# Project_Amp_RevA.net
KiCad netlist of a schematic drawn in EAGLE
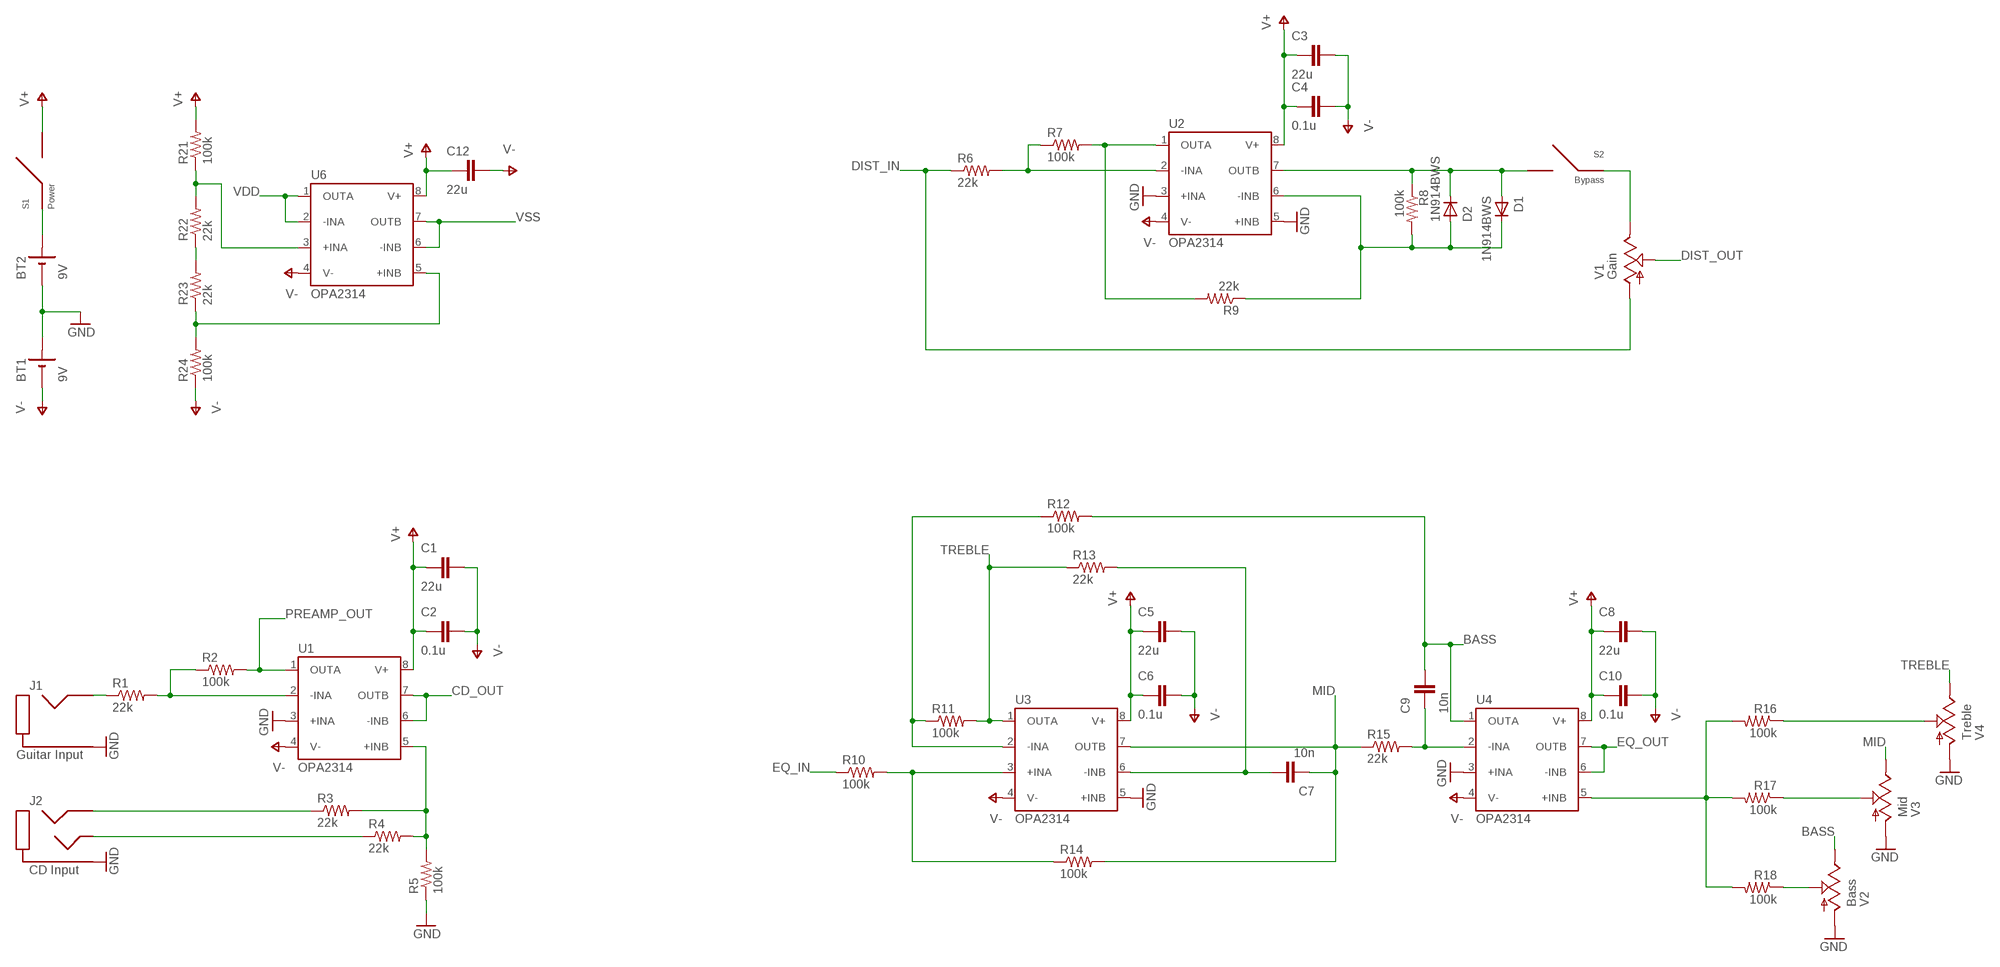
[diagram p0: schematic, sheet 1, part 1 of 2]
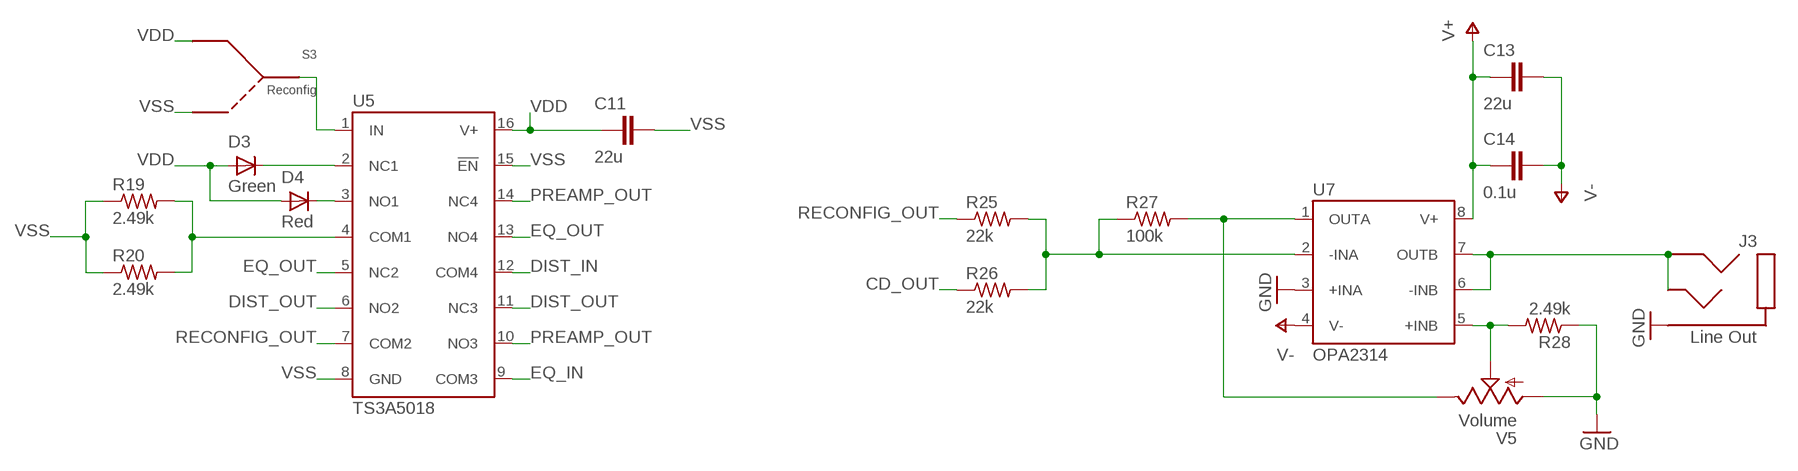
[diagram p1: schematic, sheet 1, part 2 of 2]

(export (version "E")
  (design (tool "Eeschema 10.0.6"))
  (components
    (comp (ref "BT1")
      (value "9V")
      (footprint "eagle-import:9V59X")
      (libsource (lib "eagle-import") (part "9V59X{dblquote}"))
    )
    (comp (ref "BT2")
      (value "9V")
      (footprint "eagle-import:9V59X")
      (libsource (lib "eagle-import") (part "9V59X{dblquote}"))
    )
    (comp (ref "C1")
      (value "22u")
      (footprint "eagle-import:C1206")
      (libsource (lib "eagle-import") (part "C1206"))
    )
    (comp (ref "C2")
      (value "0.1u")
      (footprint "eagle-import:C0402")
      (libsource (lib "eagle-import") (part "C0402"))
    )
    (comp (ref "C3")
      (value "22u")
      (footprint "eagle-import:C1206")
      (libsource (lib "eagle-import") (part "C1206"))
    )
    (comp (ref "C4")
      (value "0.1u")
      (footprint "eagle-import:C0402")
      (libsource (lib "eagle-import") (part "C0402"))
    )
    (comp (ref "C5")
      (value "22u")
      (footprint "eagle-import:C1206")
      (libsource (lib "eagle-import") (part "C1206"))
    )
    (comp (ref "C6")
      (value "0.1u")
      (footprint "eagle-import:C0402")
      (libsource (lib "eagle-import") (part "C0402"))
    )
    (comp (ref "C7")
      (value "10n")
      (footprint "eagle-import:ECW-F6103HL")
      (libsource (lib "eagle-import") (part "CTHRU"))
    )
    (comp (ref "C8")
      (value "22u")
      (footprint "eagle-import:C1206")
      (libsource (lib "eagle-import") (part "C1206"))
    )
    (comp (ref "C9")
      (value "10n")
      (footprint "eagle-import:ECW-F6103HL")
      (libsource (lib "eagle-import") (part "CTHRU"))
    )
    (comp (ref "C10")
      (value "0.1u")
      (footprint "eagle-import:C0402")
      (libsource (lib "eagle-import") (part "C0402"))
    )
    (comp (ref "C11")
      (value "22u")
      (footprint "eagle-import:C1206")
      (libsource (lib "eagle-import") (part "C1206"))
    )
    (comp (ref "C12")
      (value "22u")
      (footprint "eagle-import:C1206")
      (libsource (lib "eagle-import") (part "C1206"))
    )
    (comp (ref "C13")
      (value "22u")
      (footprint "eagle-import:C1206")
      (libsource (lib "eagle-import") (part "C1206"))
    )
    (comp (ref "C14")
      (value "0.1u")
      (footprint "eagle-import:C0402")
      (libsource (lib "eagle-import") (part "C0402"))
    )
    (comp (ref "D1")
      (value "1N914BWS")
      (footprint "eagle-import:SOD-323F")
      (libsource (lib "eagle-import") (part "DSOD-323F"))
    )
    (comp (ref "D2")
      (value "1N914BWS")
      (footprint "eagle-import:SOD-323F")
      (libsource (lib "eagle-import") (part "DSOD-323F"))
    )
    (comp (ref "D3")
      (value "Green")
      (footprint "eagle-import:R0402")
      (libsource (lib "eagle-import") (part "D"))
    )
    (comp (ref "D4")
      (value "Red")
      (footprint "eagle-import:R0402")
      (libsource (lib "eagle-import") (part "D"))
    )
    (comp (ref "J1")
      (value "Guitar Input")
      (footprint "eagle-import:RA49C12B")
      (libsource (lib "eagle-import") (part "RA49C12B"))
    )
    (comp (ref "J2")
      (value "CD Input")
      (footprint "eagle-import:SJ1-3513-SMT-TR")
      (libsource (lib "eagle-import") (part "SJ1-3513-SMT-TR"))
    )
    (comp (ref "J3")
      (value "Line Out")
      (footprint "eagle-import:SJ1-3513-SMT-TR")
      (libsource (lib "eagle-import") (part "SJ1-3513-SMT-TR"))
    )
    (comp (ref "R1")
      (value "22k")
      (footprint "eagle-import:R0402")
      (libsource (lib "eagle-import") (part "R0402"))
    )
    (comp (ref "R2")
      (value "100k")
      (footprint "eagle-import:R0402")
      (libsource (lib "eagle-import") (part "R0402"))
    )
    (comp (ref "R3")
      (value "22k")
      (footprint "eagle-import:R0402")
      (libsource (lib "eagle-import") (part "R0402"))
    )
    (comp (ref "R4")
      (value "22k")
      (footprint "eagle-import:R0402")
      (libsource (lib "eagle-import") (part "R0402"))
    )
    (comp (ref "R5")
      (value "100k")
      (footprint "eagle-import:R0402")
      (libsource (lib "eagle-import") (part "R0402"))
    )
    (comp (ref "R6")
      (value "22k")
      (footprint "eagle-import:R0402")
      (libsource (lib "eagle-import") (part "R0402"))
    )
    (comp (ref "R7")
      (value "100k")
      (footprint "eagle-import:R0402")
      (libsource (lib "eagle-import") (part "R0402"))
    )
    (comp (ref "R8")
      (value "100k")
      (footprint "eagle-import:R0402")
      (libsource (lib "eagle-import") (part "R0402"))
    )
    (comp (ref "R9")
      (value "22k")
      (footprint "eagle-import:R0402")
      (libsource (lib "eagle-import") (part "R0402"))
    )
    (comp (ref "R10")
      (value "100k")
      (footprint "eagle-import:R0402")
      (libsource (lib "eagle-import") (part "R0402"))
    )
    (comp (ref "R11")
      (value "100k")
      (footprint "eagle-import:R0402")
      (libsource (lib "eagle-import") (part "R0402"))
    )
    (comp (ref "R12")
      (value "100k")
      (footprint "eagle-import:R0402")
      (libsource (lib "eagle-import") (part "R0402"))
    )
    (comp (ref "R13")
      (value "22k")
      (footprint "eagle-import:R0402")
      (libsource (lib "eagle-import") (part "R0402"))
    )
    (comp (ref "R14")
      (value "100k")
      (footprint "eagle-import:R0402")
      (libsource (lib "eagle-import") (part "R0402"))
    )
    (comp (ref "R15")
      (value "22k")
      (footprint "eagle-import:R0402")
      (libsource (lib "eagle-import") (part "R0402"))
    )
    (comp (ref "R16")
      (value "100k")
      (footprint "eagle-import:R0402")
      (libsource (lib "eagle-import") (part "R0402"))
    )
    (comp (ref "R17")
      (value "100k")
      (footprint "eagle-import:R0402")
      (libsource (lib "eagle-import") (part "R0402"))
    )
    (comp (ref "R18")
      (value "100k")
      (footprint "eagle-import:R0402")
      (libsource (lib "eagle-import") (part "R0402"))
    )
    (comp (ref "R19")
      (value "2.49k")
      (footprint "eagle-import:R0402")
      (libsource (lib "eagle-import") (part "R0402"))
    )
    (comp (ref "R20")
      (value "2.49k")
      (footprint "eagle-import:R0402")
      (libsource (lib "eagle-import") (part "R0402"))
    )
    (comp (ref "R21")
      (value "100k")
      (footprint "eagle-import:R0402")
      (libsource (lib "eagle-import") (part "R0402"))
    )
    (comp (ref "R22")
      (value "22k")
      (footprint "eagle-import:R0402")
      (libsource (lib "eagle-import") (part "R0402"))
    )
    (comp (ref "R23")
      (value "22k")
      (footprint "eagle-import:R0402")
      (libsource (lib "eagle-import") (part "R0402"))
    )
    (comp (ref "R24")
      (value "100k")
      (footprint "eagle-import:R0402")
      (libsource (lib "eagle-import") (part "R0402"))
    )
    (comp (ref "R25")
      (value "22k")
      (footprint "eagle-import:R0402")
      (libsource (lib "eagle-import") (part "R0402"))
    )
    (comp (ref "R26")
      (value "22k")
      (footprint "eagle-import:R0402")
      (libsource (lib "eagle-import") (part "R0402"))
    )
    (comp (ref "R27")
      (value "100k")
      (footprint "eagle-import:R0402")
      (libsource (lib "eagle-import") (part "R0402"))
    )
    (comp (ref "R28")
      (value "2.49k")
      (footprint "eagle-import:R0402")
      (libsource (lib "eagle-import") (part "R0402"))
    )
    (comp (ref "S1")
      (value "Power")
      (footprint "eagle-import:TMS6T5B2M2RE")
      (libsource (lib "eagle-import") (part "TMS6T5B2M2RE"))
    )
    (comp (ref "S2")
      (value "Bypass")
      (footprint "eagle-import:TMS6T5B2M2RE")
      (libsource (lib "eagle-import") (part "TMS6T5B2M2RE"))
    )
    (comp (ref "S3")
      (value "Reconfig")
      (footprint "eagle-import:TMS1T5B2M2R")
      (libsource (lib "eagle-import") (part "TMS1T5B2M2RE"))
    )
    (comp (ref "U1")
      (value "OPA2314")
      (footprint "eagle-import:8-SOIC")
      (libsource (lib "eagle-import") (part "OPA2314SOIC"))
    )
    (comp (ref "U2")
      (value "OPA2314")
      (footprint "eagle-import:8-SOIC")
      (libsource (lib "eagle-import") (part "OPA2314SOIC"))
    )
    (comp (ref "U3")
      (value "OPA2314")
      (footprint "eagle-import:8-SOIC")
      (libsource (lib "eagle-import") (part "OPA2314SOIC"))
    )
    (comp (ref "U4")
      (value "OPA2314")
      (footprint "eagle-import:8-SOIC")
      (libsource (lib "eagle-import") (part "OPA2314SOIC"))
    )
    (comp (ref "U5")
      (value "TS3A5018")
      (footprint "eagle-import:16-SOIC")
      (libsource (lib "eagle-import") (part "TS3A501816-SOIC"))
    )
    (comp (ref "U6")
      (value "OPA2314")
      (footprint "eagle-import:8-SOIC")
      (libsource (lib "eagle-import") (part "OPA2314SOIC"))
    )
    (comp (ref "U7")
      (value "OPA2314")
      (footprint "eagle-import:8-SOIC")
      (libsource (lib "eagle-import") (part "OPA2314SOIC"))
    )
    (comp (ref "V1")
      (value "Gain")
      (footprint "eagle-import:P0915N-EC15BR10K")
      (libsource (lib "eagle-import") (part "POT"))
    )
    (comp (ref "V2")
      (value "Bass")
      (footprint "eagle-import:P0915N-EC15BR10K")
      (libsource (lib "eagle-import") (part "POT"))
    )
    (comp (ref "V3")
      (value "Mid")
      (footprint "eagle-import:P0915N-EC15BR10K")
      (libsource (lib "eagle-import") (part "POT"))
    )
    (comp (ref "V4")
      (value "Treble")
      (footprint "eagle-import:P0915N-EC15BR10K")
      (libsource (lib "eagle-import") (part "POT"))
    )
    (comp (ref "V5")
      (value "Volume")
      (footprint "eagle-import:P0915N-EC15BR10K")
      (libsource (lib "eagle-import") (part "POT"))
    )
  )
  (nets
    (net (code "1") (name "/BASS") (class "Default")
      (node (ref "C9") (pin "1") (pinfunction "1_1") (pintype "passive"))
      (node (ref "R12") (pin "2") (pinfunction "2_2") (pintype "passive"))
      (node (ref "U4") (pin "1") (pinfunction "OUTA_1") (pintype "output"))
      (node (ref "V2") (pin "3") (pinfunction "E_3") (pintype "passive"))
    )
    (net (code "2") (name "/CD_OUT") (class "Default")
      (node (ref "R26") (pin "1") (pinfunction "1_1") (pintype "passive"))
      (node (ref "U1") (pin "6") (pinfunction "-INB_6") (pintype "input"))
      (node (ref "U1") (pin "7") (pinfunction "OUTB_7") (pintype "output"))
    )
    (net (code "3") (name "/DIST_IN") (class "Default")
      (node (ref "R6") (pin "1") (pinfunction "1_1") (pintype "passive"))
      (node (ref "U5") (pin "12") (pinfunction "COM4_12") (pintype "bidirectional"))
      (node (ref "V1") (pin "1") (pinfunction "A_1") (pintype "passive"))
    )
    (net (code "4") (name "/DIST_OUT") (class "Default")
      (node (ref "U5") (pin "11") (pinfunction "NC3_11") (pintype "bidirectional"))
      (node (ref "U5") (pin "6") (pinfunction "NO2_6") (pintype "bidirectional"))
      (node (ref "V1") (pin "2") (pinfunction "S_2") (pintype "passive"))
    )
    (net (code "5") (name "/EQ_IN") (class "Default")
      (node (ref "R10") (pin "1") (pinfunction "1_1") (pintype "passive"))
      (node (ref "U5") (pin "9") (pinfunction "COM3_9") (pintype "bidirectional"))
    )
    (net (code "6") (name "/EQ_OUT") (class "Default")
      (node (ref "U4") (pin "6") (pinfunction "-INB_6") (pintype "input"))
      (node (ref "U4") (pin "7") (pinfunction "OUTB_7") (pintype "output"))
      (node (ref "U5") (pin "13") (pinfunction "NO4_13") (pintype "bidirectional"))
      (node (ref "U5") (pin "5") (pinfunction "NC2_5") (pintype "bidirectional"))
    )
    (net (code "7") (name "/MID") (class "Default")
      (node (ref "C7") (pin "2") (pinfunction "2_2") (pintype "passive"))
      (node (ref "R14") (pin "2") (pinfunction "2_2") (pintype "passive"))
      (node (ref "R15") (pin "1") (pinfunction "1_1") (pintype "passive"))
      (node (ref "U3") (pin "7") (pinfunction "OUTB_7") (pintype "output"))
      (node (ref "V3") (pin "3") (pinfunction "E_3") (pintype "passive"))
    )
    (net (code "8") (name "/PREAMP_OUT") (class "Default")
      (node (ref "R2") (pin "2") (pinfunction "2_2") (pintype "passive"))
      (node (ref "U1") (pin "1") (pinfunction "OUTA_1") (pintype "output"))
      (node (ref "U5") (pin "10") (pinfunction "NO3_10") (pintype "bidirectional"))
      (node (ref "U5") (pin "14") (pinfunction "NC4_14") (pintype "bidirectional"))
    )
    (net (code "9") (name "/RECONFIG_OUT") (class "Default")
      (node (ref "R25") (pin "1") (pinfunction "1_1") (pintype "passive"))
      (node (ref "U5") (pin "7") (pinfunction "COM2_7") (pintype "bidirectional"))
    )
    (net (code "10") (name "/TREBLE") (class "Default")
      (node (ref "R11") (pin "2") (pinfunction "2_2") (pintype "passive"))
      (node (ref "R13") (pin "1") (pinfunction "1_1") (pintype "passive"))
      (node (ref "U3") (pin "1") (pinfunction "OUTA_1") (pintype "output"))
      (node (ref "V4") (pin "3") (pinfunction "E_3") (pintype "passive"))
    )
    (net (code "11") (name "/VDD") (class "Default")
      (node (ref "C11") (pin "2") (pinfunction "2_2") (pintype "passive"))
      (node (ref "D3") (pin "1") (pinfunction "A_1") (pintype "passive"))
      (node (ref "D4") (pin "1") (pinfunction "A_1") (pintype "passive"))
      (node (ref "S3") (pin "3") (pinfunction "POS1_3") (pintype "passive"))
      (node (ref "U5") (pin "16") (pinfunction "V+_16") (pintype "power_in"))
      (node (ref "U6") (pin "1") (pinfunction "OUTA_1") (pintype "output"))
      (node (ref "U6") (pin "2") (pinfunction "-INA_2") (pintype "input"))
    )
    (net (code "12") (name "/VSS") (class "Default")
      (node (ref "C11") (pin "1") (pinfunction "1_1") (pintype "passive"))
      (node (ref "R19") (pin "1") (pinfunction "1_1") (pintype "passive"))
      (node (ref "R20") (pin "1") (pinfunction "1_1") (pintype "passive"))
      (node (ref "S3") (pin "1") (pinfunction "POS2_1") (pintype "passive"))
      (node (ref "U5") (pin "15") (pinfunction "~{EN}_15") (pintype "input"))
      (node (ref "U5") (pin "8") (pinfunction "GND_8") (pintype "power_in"))
      (node (ref "U6") (pin "6") (pinfunction "-INB_6") (pintype "input"))
      (node (ref "U6") (pin "7") (pinfunction "OUTB_7") (pintype "output"))
    )
    (net (code "13") (name "GND") (class "Default")
      (node (ref "BT1") (pin "4") (pinfunction "+_4") (pintype "passive"))
      (node (ref "BT1") (pin "5") (pinfunction "+_5") (pintype "passive"))
      (node (ref "BT1") (pin "6") (pinfunction "+_6") (pintype "passive"))
      (node (ref "BT2") (pin "1") (pinfunction "-_1") (pintype "passive"))
      (node (ref "BT2") (pin "2") (pinfunction "-_2") (pintype "passive"))
      (node (ref "BT2") (pin "3") (pinfunction "-_3") (pintype "passive"))
      (node (ref "J1") (pin "S1") (pinfunction "COM_S1") (pintype "bidirectional"))
      (node (ref "J1") (pin "S2") (pinfunction "COM_S2") (pintype "bidirectional"))
      (node (ref "J2") (pin "1") (pinfunction "COM_1") (pintype "bidirectional"))
      (node (ref "J3") (pin "1") (pinfunction "COM_1") (pintype "bidirectional"))
      (node (ref "R28") (pin "1") (pinfunction "1_1") (pintype "passive"))
      (node (ref "R5") (pin "1") (pinfunction "1_1") (pintype "passive"))
      (node (ref "U1") (pin "3") (pinfunction "+INA_3") (pintype "input"))
      (node (ref "U2") (pin "3") (pinfunction "+INA_3") (pintype "input"))
      (node (ref "U2") (pin "5") (pinfunction "+INB_5") (pintype "input"))
      (node (ref "U3") (pin "5") (pinfunction "+INB_5") (pintype "input"))
      (node (ref "U4") (pin "3") (pinfunction "+INA_3") (pintype "input"))
      (node (ref "U7") (pin "3") (pinfunction "+INA_3") (pintype "input"))
      (node (ref "V2") (pin "1") (pinfunction "A_1") (pintype "passive"))
      (node (ref "V3") (pin "1") (pinfunction "A_1") (pintype "passive"))
      (node (ref "V4") (pin "1") (pinfunction "A_1") (pintype "passive"))
      (node (ref "V5") (pin "1") (pinfunction "A_1") (pintype "passive"))
    )
    (net (code "14") (name "Net-(D1-A)") (class "Default")
      (node (ref "D1") (pin "2") (pinfunction "A_2") (pintype "passive"))
      (node (ref "D2") (pin "1") (pinfunction "C_1") (pintype "passive"))
      (node (ref "R8") (pin "1") (pinfunction "1_1") (pintype "passive"))
      (node (ref "S2") (pin "1") (pinfunction "P$2_1") (pintype "passive"))
      (node (ref "U2") (pin "7") (pinfunction "OUTB_7") (pintype "output"))
    )
    (net (code "15") (name "Net-(D1-C)") (class "Default")
      (node (ref "D1") (pin "1") (pinfunction "C_1") (pintype "passive"))
      (node (ref "D2") (pin "2") (pinfunction "A_2") (pintype "passive"))
      (node (ref "R8") (pin "2") (pinfunction "2_2") (pintype "passive"))
      (node (ref "R9") (pin "1") (pinfunction "1_1") (pintype "passive"))
      (node (ref "U2") (pin "6") (pinfunction "-INB_6") (pintype "input"))
    )
    (net (code "16") (name "Net-(D3-C)") (class "Default")
      (node (ref "D3") (pin "2") (pinfunction "C_2") (pintype "passive"))
      (node (ref "U5") (pin "2") (pinfunction "NC1_2") (pintype "bidirectional"))
    )
    (net (code "17") (name "Net-(D4-C)") (class "Default")
      (node (ref "D4") (pin "2") (pinfunction "C_2") (pintype "passive"))
      (node (ref "U5") (pin "3") (pinfunction "NO1_3") (pintype "bidirectional"))
    )
    (net (code "18") (name "Net-(J1-SIG)") (class "Default")
      (node (ref "J1") (pin "T") (pinfunction "SIG_T") (pintype "bidirectional"))
      (node (ref "R1") (pin "1") (pinfunction "1_1") (pintype "passive"))
    )
    (net (code "19") (name "Net-(J2-LEFT)") (class "Default")
      (node (ref "J2") (pin "2") (pinfunction "LEFT_2") (pintype "bidirectional"))
      (node (ref "R4") (pin "1") (pinfunction "1_1") (pintype "passive"))
    )
    (net (code "20") (name "Net-(J2-RIGHT)") (class "Default")
      (node (ref "J2") (pin "3") (pinfunction "RIGHT_3") (pintype "bidirectional"))
      (node (ref "R3") (pin "1") (pinfunction "1_1") (pintype "passive"))
    )
    (net (code "21") (name "Net-(J3-LEFT)") (class "Default")
      (node (ref "J3") (pin "2") (pinfunction "LEFT_2") (pintype "bidirectional"))
      (node (ref "J3") (pin "3") (pinfunction "RIGHT_3") (pintype "bidirectional"))
      (node (ref "U7") (pin "6") (pinfunction "-INB_6") (pintype "input"))
      (node (ref "U7") (pin "7") (pinfunction "OUTB_7") (pintype "output"))
    )
    (net (code "22") (name "Net-(R22-Pad1)") (class "Default")
      (node (ref "R22") (pin "1") (pinfunction "1_1") (pintype "passive"))
      (node (ref "R23") (pin "2") (pinfunction "2_2") (pintype "passive"))
    )
    (net (code "23") (name "Net-(S1-P$1)") (class "Default")
      (node (ref "BT2") (pin "4") (pinfunction "+_4") (pintype "passive"))
      (node (ref "BT2") (pin "5") (pinfunction "+_5") (pintype "passive"))
      (node (ref "BT2") (pin "6") (pinfunction "+_6") (pintype "passive"))
      (node (ref "S1") (pin "3") (pinfunction "P$1_3") (pintype "passive"))
    )
    (net (code "24") (name "Net-(S2-P$1)") (class "Default")
      (node (ref "S2") (pin "3") (pinfunction "P$1_3") (pintype "passive"))
      (node (ref "V1") (pin "3") (pinfunction "E_3") (pintype "passive"))
    )
    (net (code "25") (name "Net-(S3-COM)") (class "Default")
      (node (ref "S3") (pin "2") (pinfunction "COM_2") (pintype "passive"))
      (node (ref "U5") (pin "1") (pinfunction "IN_1") (pintype "input"))
    )
    (net (code "26") (name "Net-(U1-+INB)") (class "Default")
      (node (ref "R3") (pin "2") (pinfunction "2_2") (pintype "passive"))
      (node (ref "R4") (pin "2") (pinfunction "2_2") (pintype "passive"))
      (node (ref "R5") (pin "2") (pinfunction "2_2") (pintype "passive"))
      (node (ref "U1") (pin "5") (pinfunction "+INB_5") (pintype "input"))
    )
    (net (code "27") (name "Net-(U1--INA)") (class "Default")
      (node (ref "R1") (pin "2") (pinfunction "2_2") (pintype "passive"))
      (node (ref "R2") (pin "1") (pinfunction "1_1") (pintype "passive"))
      (node (ref "U1") (pin "2") (pinfunction "-INA_2") (pintype "input"))
    )
    (net (code "28") (name "Net-(U2--INA)") (class "Default")
      (node (ref "R6") (pin "2") (pinfunction "2_2") (pintype "passive"))
      (node (ref "R7") (pin "1") (pinfunction "1_1") (pintype "passive"))
      (node (ref "U2") (pin "2") (pinfunction "-INA_2") (pintype "input"))
    )
    (net (code "29") (name "Net-(U2-OUTA)") (class "Default")
      (node (ref "R7") (pin "2") (pinfunction "2_2") (pintype "passive"))
      (node (ref "R9") (pin "2") (pinfunction "2_2") (pintype "passive"))
      (node (ref "U2") (pin "1") (pinfunction "OUTA_1") (pintype "output"))
    )
    (net (code "30") (name "Net-(U3-+INA)") (class "Default")
      (node (ref "R10") (pin "2") (pinfunction "2_2") (pintype "passive"))
      (node (ref "R14") (pin "1") (pinfunction "1_1") (pintype "passive"))
      (node (ref "U3") (pin "3") (pinfunction "+INA_3") (pintype "input"))
    )
    (net (code "31") (name "Net-(U3--INA)") (class "Default")
      (node (ref "R11") (pin "1") (pinfunction "1_1") (pintype "passive"))
      (node (ref "R12") (pin "1") (pinfunction "1_1") (pintype "passive"))
      (node (ref "U3") (pin "2") (pinfunction "-INA_2") (pintype "input"))
    )
    (net (code "32") (name "Net-(U3--INB)") (class "Default")
      (node (ref "C7") (pin "1") (pinfunction "1_1") (pintype "passive"))
      (node (ref "R13") (pin "2") (pinfunction "2_2") (pintype "passive"))
      (node (ref "U3") (pin "6") (pinfunction "-INB_6") (pintype "input"))
    )
    (net (code "33") (name "Net-(U4-+INB)") (class "Default")
      (node (ref "R16") (pin "2") (pinfunction "2_2") (pintype "passive"))
      (node (ref "R17") (pin "2") (pinfunction "2_2") (pintype "passive"))
      (node (ref "R18") (pin "2") (pinfunction "2_2") (pintype "passive"))
      (node (ref "U4") (pin "5") (pinfunction "+INB_5") (pintype "input"))
    )
    (net (code "34") (name "Net-(U4--INA)") (class "Default")
      (node (ref "C9") (pin "2") (pinfunction "2_2") (pintype "passive"))
      (node (ref "R15") (pin "2") (pinfunction "2_2") (pintype "passive"))
      (node (ref "U4") (pin "2") (pinfunction "-INA_2") (pintype "input"))
    )
    (net (code "35") (name "Net-(U5-COM1)") (class "Default")
      (node (ref "R19") (pin "2") (pinfunction "2_2") (pintype "passive"))
      (node (ref "R20") (pin "2") (pinfunction "2_2") (pintype "passive"))
      (node (ref "U5") (pin "4") (pinfunction "COM1_4") (pintype "bidirectional"))
    )
    (net (code "36") (name "Net-(U6-+INA)") (class "Default")
      (node (ref "R21") (pin "1") (pinfunction "1_1") (pintype "passive"))
      (node (ref "R22") (pin "2") (pinfunction "2_2") (pintype "passive"))
      (node (ref "U6") (pin "3") (pinfunction "+INA_3") (pintype "input"))
    )
    (net (code "37") (name "Net-(U6-+INB)") (class "Default")
      (node (ref "R23") (pin "1") (pinfunction "1_1") (pintype "passive"))
      (node (ref "R24") (pin "2") (pinfunction "2_2") (pintype "passive"))
      (node (ref "U6") (pin "5") (pinfunction "+INB_5") (pintype "input"))
    )
    (net (code "38") (name "Net-(U7-+INB)") (class "Default")
      (node (ref "R28") (pin "2") (pinfunction "2_2") (pintype "passive"))
      (node (ref "U7") (pin "5") (pinfunction "+INB_5") (pintype "input"))
      (node (ref "V5") (pin "2") (pinfunction "S_2") (pintype "passive"))
    )
    (net (code "39") (name "Net-(U7--INA)") (class "Default")
      (node (ref "R25") (pin "2") (pinfunction "2_2") (pintype "passive"))
      (node (ref "R26") (pin "2") (pinfunction "2_2") (pintype "passive"))
      (node (ref "R27") (pin "1") (pinfunction "1_1") (pintype "passive"))
      (node (ref "U7") (pin "2") (pinfunction "-INA_2") (pintype "input"))
    )
    (net (code "40") (name "Net-(U7-OUTA)") (class "Default")
      (node (ref "R27") (pin "2") (pinfunction "2_2") (pintype "passive"))
      (node (ref "U7") (pin "1") (pinfunction "OUTA_1") (pintype "output"))
      (node (ref "V5") (pin "3") (pinfunction "E_3") (pintype "passive"))
    )
    (net (code "41") (name "Net-(V2-S)") (class "Default")
      (node (ref "R18") (pin "1") (pinfunction "1_1") (pintype "passive"))
      (node (ref "V2") (pin "2") (pinfunction "S_2") (pintype "passive"))
    )
    (net (code "42") (name "Net-(V3-S)") (class "Default")
      (node (ref "R17") (pin "1") (pinfunction "1_1") (pintype "passive"))
      (node (ref "V3") (pin "2") (pinfunction "S_2") (pintype "passive"))
    )
    (net (code "43") (name "Net-(V4-S)") (class "Default")
      (node (ref "R16") (pin "1") (pinfunction "1_1") (pintype "passive"))
      (node (ref "V4") (pin "2") (pinfunction "S_2") (pintype "passive"))
    )
    (net (code "44") (name "V+") (class "Default")
      (node (ref "C1") (pin "2") (pinfunction "2_2") (pintype "passive"))
      (node (ref "C10") (pin "2") (pinfunction "2_2") (pintype "passive"))
      (node (ref "C12") (pin "2") (pinfunction "2_2") (pintype "passive"))
      (node (ref "C13") (pin "2") (pinfunction "2_2") (pintype "passive"))
      (node (ref "C14") (pin "2") (pinfunction "2_2") (pintype "passive"))
      (node (ref "C2") (pin "2") (pinfunction "2_2") (pintype "passive"))
      (node (ref "C3") (pin "2") (pinfunction "2_2") (pintype "passive"))
      (node (ref "C4") (pin "2") (pinfunction "2_2") (pintype "passive"))
      (node (ref "C5") (pin "2") (pinfunction "2_2") (pintype "passive"))
      (node (ref "C6") (pin "2") (pinfunction "2_2") (pintype "passive"))
      (node (ref "C8") (pin "2") (pinfunction "2_2") (pintype "passive"))
      (node (ref "R21") (pin "2") (pinfunction "2_2") (pintype "passive"))
      (node (ref "S1") (pin "1") (pinfunction "P$2_1") (pintype "passive"))
      (node (ref "U1") (pin "8") (pinfunction "V+_8") (pintype "power_in"))
      (node (ref "U2") (pin "8") (pinfunction "V+_8") (pintype "power_in"))
      (node (ref "U3") (pin "8") (pinfunction "V+_8") (pintype "power_in"))
      (node (ref "U4") (pin "8") (pinfunction "V+_8") (pintype "power_in"))
      (node (ref "U6") (pin "8") (pinfunction "V+_8") (pintype "power_in"))
      (node (ref "U7") (pin "8") (pinfunction "V+_8") (pintype "power_in"))
    )
    (net (code "45") (name "V-") (class "Default")
      (node (ref "BT1") (pin "1") (pinfunction "-_1") (pintype "passive"))
      (node (ref "BT1") (pin "2") (pinfunction "-_2") (pintype "passive"))
      (node (ref "BT1") (pin "3") (pinfunction "-_3") (pintype "passive"))
      (node (ref "C1") (pin "1") (pinfunction "1_1") (pintype "passive"))
      (node (ref "C10") (pin "1") (pinfunction "1_1") (pintype "passive"))
      (node (ref "C12") (pin "1") (pinfunction "1_1") (pintype "passive"))
      (node (ref "C13") (pin "1") (pinfunction "1_1") (pintype "passive"))
      (node (ref "C14") (pin "1") (pinfunction "1_1") (pintype "passive"))
      (node (ref "C2") (pin "1") (pinfunction "1_1") (pintype "passive"))
      (node (ref "C3") (pin "1") (pinfunction "1_1") (pintype "passive"))
      (node (ref "C4") (pin "1") (pinfunction "1_1") (pintype "passive"))
      (node (ref "C5") (pin "1") (pinfunction "1_1") (pintype "passive"))
      (node (ref "C6") (pin "1") (pinfunction "1_1") (pintype "passive"))
      (node (ref "C8") (pin "1") (pinfunction "1_1") (pintype "passive"))
      (node (ref "R24") (pin "1") (pinfunction "1_1") (pintype "passive"))
      (node (ref "U1") (pin "4") (pinfunction "V-_4") (pintype "power_in"))
      (node (ref "U2") (pin "4") (pinfunction "V-_4") (pintype "power_in"))
      (node (ref "U3") (pin "4") (pinfunction "V-_4") (pintype "power_in"))
      (node (ref "U4") (pin "4") (pinfunction "V-_4") (pintype "power_in"))
      (node (ref "U6") (pin "4") (pinfunction "V-_4") (pintype "power_in"))
      (node (ref "U7") (pin "4") (pinfunction "V-_4") (pintype "power_in"))
    )
  )
)
